# Power.net
KiCad netlist of a schematic drawn in Altium Designer
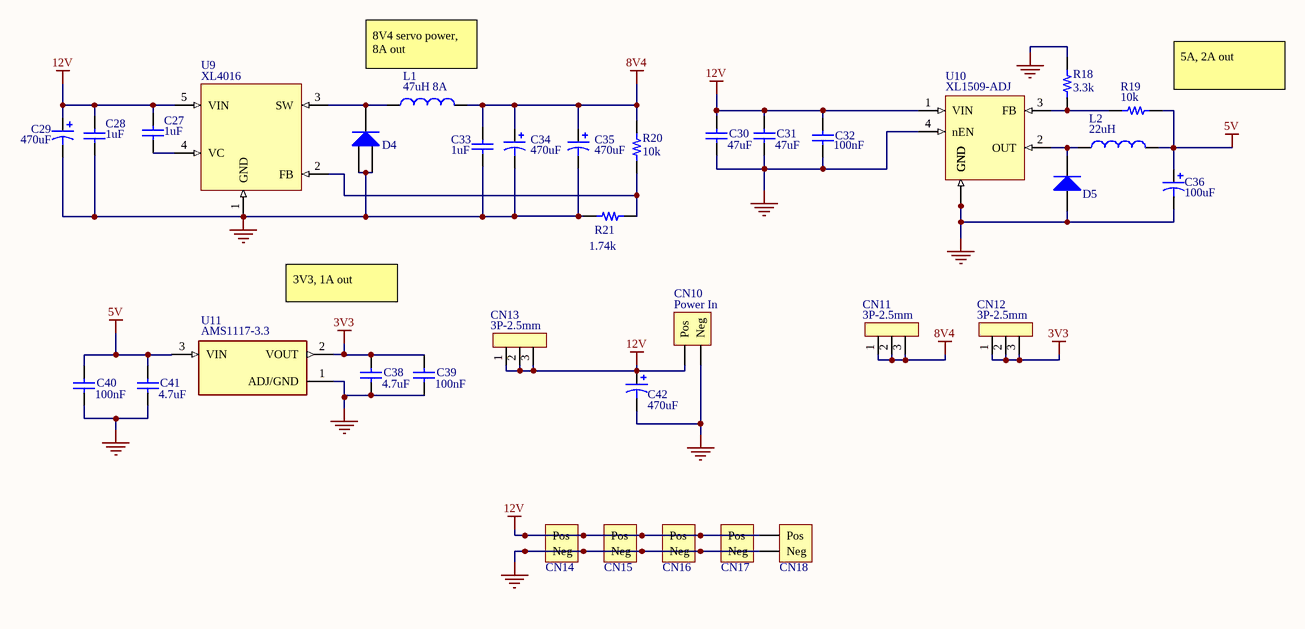
[diagram p0: Power.SchDoc]

(export (version "E")
  (design (tool "Eeschema 10.0.6"))
  (components
    (comp (ref "C27")
      (value "1uF")
      (footprint "0402")
      (fields (field (name "Comment") "Cap") (field (name "PUBLISHER") "Altium Limited"))
      (libsource (lib "Parts") (part "Cap"))
    )
    (comp (ref "C28")
      (value "1uF")
      (footprint "0402")
      (fields (field (name "Comment") "Cap") (field (name "PUBLISHER") "Altium Limited"))
      (libsource (lib "Parts") (part "Cap"))
    )
    (comp (ref "C29")
      (value "470uF")
      (footprint "10x12mm-Electrolytic")
      (libsource (lib "Parts") (part "Polarised Capacitor"))
    )
    (comp (ref "C30")
      (value "47uF")
      (footprint "1206")
      (fields (field (name "Comment") "Cap") (field (name "PUBLISHER") "Altium Limited"))
      (libsource (lib "Parts") (part "Cap"))
    )
    (comp (ref "C31")
      (value "47uF")
      (footprint "1206")
      (fields (field (name "Comment") "Cap") (field (name "PUBLISHER") "Altium Limited"))
      (libsource (lib "Parts") (part "Cap"))
    )
    (comp (ref "C32")
      (value "100nF")
      (footprint "0402")
      (fields (field (name "Comment") "Cap") (field (name "PUBLISHER") "Altium Limited"))
      (libsource (lib "Parts") (part "Cap"))
    )
    (comp (ref "C33")
      (value "1uF")
      (footprint "0402")
      (fields (field (name "Comment") "Cap") (field (name "PUBLISHER") "Altium Limited"))
      (libsource (lib "Parts") (part "Cap"))
    )
    (comp (ref "C34")
      (value "470uF")
      (footprint "10x12mm-Electrolytic")
      (libsource (lib "Parts") (part "Polarised Capacitor"))
    )
    (comp (ref "C35")
      (value "470uF")
      (footprint "10x12mm-Electrolytic")
      (libsource (lib "Parts") (part "Polarised Capacitor"))
    )
    (comp (ref "C36")
      (value "100uF")
      (footprint "10x12mm-Electrolytic")
      (libsource (lib "Parts") (part "Polarised Capacitor"))
    )
    (comp (ref "C38")
      (value "4.7uF")
      (footprint "0805 - duplicate")
      (fields (field (name "Comment") "Cap") (field (name "PUBLISHER") "Altium Limited"))
      (libsource (lib "Parts") (part "Cap"))
    )
    (comp (ref "C39")
      (value "100nF")
      (footprint "0402")
      (fields (field (name "Comment") "Cap") (field (name "PUBLISHER") "Altium Limited"))
      (libsource (lib "Parts") (part "Cap"))
    )
    (comp (ref "C40")
      (value "100nF")
      (footprint "0402")
      (fields (field (name "Comment") "Cap") (field (name "PUBLISHER") "Altium Limited"))
      (libsource (lib "Parts") (part "Cap"))
    )
    (comp (ref "C41")
      (value "4.7uF")
      (footprint "0805 - duplicate")
      (fields (field (name "Comment") "Cap") (field (name "PUBLISHER") "Altium Limited"))
      (libsource (lib "Parts") (part "Cap"))
    )
    (comp (ref "C42")
      (value "470uF")
      (footprint "10x12mm-Electrolytic")
      (libsource (lib "Parts") (part "Polarised Capacitor"))
    )
    (comp (ref "CN10")
      (value "Power In")
      (footprint "Power_Leads")
      (libsource (lib "") (part "JST_Leads_In_1"))
    )
    (comp (ref "CN11") (value "3P-2.5mm") (footprint "2.5mm-3P") (libsource (lib "Parts") (part "3P-2.5mm")))
    (comp (ref "CN12") (value "3P-2.5mm") (footprint "2.5mm-3P") (libsource (lib "Parts") (part "3P-2.5mm")))
    (comp (ref "CN13") (value "3P-2.5mm") (footprint "2.5mm-3P") (libsource (lib "Parts") (part "3P-2.5mm")))
    (comp (ref "CN14")
      (value "JST_Leads_In")
      (footprint "Power_Leads")
      (libsource (lib "Parts") (part "JST_Leads_In"))
    )
    (comp (ref "CN15")
      (value "JST_Leads_In")
      (footprint "Power_Leads")
      (libsource (lib "Parts") (part "JST_Leads_In"))
    )
    (comp (ref "CN16")
      (value "JST_Leads_In")
      (footprint "Power_Leads")
      (libsource (lib "Parts") (part "JST_Leads_In"))
    )
    (comp (ref "CN17")
      (value "JST_Leads_In")
      (footprint "Power_Leads")
      (libsource (lib "Parts") (part "JST_Leads_In"))
    )
    (comp (ref "CN18")
      (value "JST_Leads_In")
      (footprint "Power_Leads")
      (libsource (lib "Parts") (part "JST_Leads_In"))
    )
    (comp (ref "D4")
      (value "Diode")
      (footprint "PowerDi5")
      (fields (field (name "PUBLISHER") "Altium Limited"))
      (libsource (lib "Parts") (part "Diode"))
    )
    (comp (ref "D5")
      (value "SS24")
      (footprint "DO-214AA")
      (description "2A Schottky Diode")
      (libsource (lib "Parts") (part "SS24"))
    )
    (comp (ref "L1")
      (value "47uH 8A")
      (footprint "18x16-9-Inductor")
      (description "TMPC1707")
      (libsource (lib "Parts") (part "SMD Inductor 18x16.9"))
    )
    (comp (ref "L2")
      (value "22uH")
      (footprint "71x66-Inductor")
      (libsource (lib "Parts") (part "22uH Inductor, 7.1*6.6"))
    )
    (comp (ref "R18")
      (value "3.3k")
      (footprint "0805 - duplicate")
      (libsource (lib "Parts") (part "Resistor"))
    )
    (comp (ref "R19")
      (value "10k")
      (footprint "0805 - duplicate")
      (libsource (lib "Parts") (part "Resistor"))
    )
    (comp (ref "R20")
      (value "10k")
      (footprint "0805 - duplicate")
      (libsource (lib "Parts") (part "Resistor"))
    )
    (comp (ref "R21")
      (value "1.74k")
      (footprint "0805 - duplicate")
      (libsource (lib "Parts") (part "Resistor"))
    )
    (comp (ref "U9")
      (value "XL4016")
      (footprint "TO220-5L")
      (description "8A Buck COnverter")
      (libsource (lib "Parts") (part "XL4016"))
    )
    (comp (ref "U10")
      (value "XL1509-ADJ")
      (footprint "SOP8-MT3420")
      (libsource (lib "Parts") (part "XL1509-5"))
    )
    (comp (ref "U11")
      (value "AMS1117-3.3")
      (footprint "SOT229P700X180-4N")
      (description "Sot223/Pkg 1-Amp 3.3-Volt Low Drop Out Voltage Regulatator")
      (fields (field (name "MF") "Advanced Monolithic Systems"))
      (libsource (lib "Parts") (part "AMS1117-3.3"))
    )
  )
  (nets
    (net (code "1") (name "3V3") (class "Default")
      (node (ref "C38") (pin "2") (pinfunction "2_2") (pintype "passive"))
      (node (ref "C39") (pin "2") (pinfunction "2_2") (pintype "passive"))
      (node (ref "CN12") (pin "1") (pintype "passive"))
      (node (ref "CN12") (pin "2") (pintype "passive"))
      (node (ref "CN12") (pin "3") (pintype "passive"))
      (node (ref "U11") (pin "2") (pinfunction "VOUT_2") (pintype "output"))
    )
    (net (code "2") (name "5V") (class "Default")
      (node (ref "C36") (pin "1") (pinfunction "1_1") (pintype "passive"))
      (node (ref "C40") (pin "2") (pinfunction "2_2") (pintype "passive"))
      (node (ref "C41") (pin "2") (pinfunction "2_2") (pintype "passive"))
      (node (ref "L2") (pin "2") (pinfunction "2_2") (pintype "passive"))
      (node (ref "R19") (pin "2") (pinfunction "2_2") (pintype "passive"))
      (node (ref "U11") (pin "3") (pinfunction "VIN_3") (pintype "input"))
    )
    (net (code "3") (name "8V4") (class "Default")
      (node (ref "C33") (pin "2") (pinfunction "2_2") (pintype "passive"))
      (node (ref "C34") (pin "1") (pinfunction "1_1") (pintype "passive"))
      (node (ref "C35") (pin "1") (pinfunction "1_1") (pintype "passive"))
      (node (ref "CN11") (pin "1") (pintype "passive"))
      (node (ref "CN11") (pin "2") (pintype "passive"))
      (node (ref "CN11") (pin "3") (pintype "passive"))
      (node (ref "L1") (pin "2") (pinfunction "2_2") (pintype "passive"))
      (node (ref "R20") (pin "2") (pinfunction "2_2") (pintype "passive"))
    )
    (net (code "4") (name "12V") (class "Default")
      (node (ref "C27") (pin "2") (pinfunction "2_2") (pintype "passive"))
      (node (ref "C28") (pin "2") (pinfunction "2_2") (pintype "passive"))
      (node (ref "C29") (pin "1") (pinfunction "1_1") (pintype "passive"))
      (node (ref "C30") (pin "2") (pinfunction "2_2") (pintype "passive"))
      (node (ref "C31") (pin "2") (pinfunction "2_2") (pintype "passive"))
      (node (ref "C32") (pin "2") (pinfunction "2_2") (pintype "passive"))
      (node (ref "C42") (pin "1") (pinfunction "1_1") (pintype "passive"))
      (node (ref "CN10") (pin "A") (pinfunction "Pos_A") (pintype "passive"))
      (node (ref "CN13") (pin "1") (pintype "passive"))
      (node (ref "CN13") (pin "2") (pintype "passive"))
      (node (ref "CN13") (pin "3") (pintype "passive"))
      (node (ref "CN14") (pin "A") (pinfunction "Pos_A") (pintype "passive"))
      (node (ref "CN15") (pin "A") (pinfunction "Pos_A") (pintype "passive"))
      (node (ref "CN16") (pin "A") (pinfunction "Pos_A") (pintype "passive"))
      (node (ref "CN17") (pin "A") (pinfunction "Pos_A") (pintype "passive"))
      (node (ref "CN18") (pin "A") (pinfunction "Pos_A") (pintype "passive"))
      (node (ref "U10") (pin "1") (pinfunction "VIN_1") (pintype "input"))
      (node (ref "U9") (pin "5") (pinfunction "VIN_5") (pintype "input"))
    )
    (net (code "5") (name "GND") (class "Default")
      (node (ref "C28") (pin "1") (pinfunction "1_1") (pintype "passive"))
      (node (ref "C29") (pin "2") (pinfunction "2_2") (pintype "passive"))
      (node (ref "C30") (pin "1") (pinfunction "1_1") (pintype "passive"))
      (node (ref "C31") (pin "1") (pinfunction "1_1") (pintype "passive"))
      (node (ref "C32") (pin "1") (pinfunction "1_1") (pintype "passive"))
      (node (ref "C33") (pin "1") (pinfunction "1_1") (pintype "passive"))
      (node (ref "C34") (pin "2") (pinfunction "2_2") (pintype "passive"))
      (node (ref "C35") (pin "2") (pinfunction "2_2") (pintype "passive"))
      (node (ref "C36") (pin "2") (pinfunction "2_2") (pintype "passive"))
      (node (ref "C38") (pin "1") (pinfunction "1_1") (pintype "passive"))
      (node (ref "C39") (pin "1") (pinfunction "1_1") (pintype "passive"))
      (node (ref "C40") (pin "1") (pinfunction "1_1") (pintype "passive"))
      (node (ref "C41") (pin "1") (pinfunction "1_1") (pintype "passive"))
      (node (ref "C42") (pin "2") (pinfunction "2_2") (pintype "passive"))
      (node (ref "CN10") (pin "K") (pinfunction "Neg_K") (pintype "passive"))
      (node (ref "CN14") (pin "K") (pinfunction "Neg_K") (pintype "passive"))
      (node (ref "CN15") (pin "K") (pinfunction "Neg_K") (pintype "passive"))
      (node (ref "CN16") (pin "K") (pinfunction "Neg_K") (pintype "passive"))
      (node (ref "CN17") (pin "K") (pinfunction "Neg_K") (pintype "passive"))
      (node (ref "CN18") (pin "K") (pinfunction "Neg_K") (pintype "passive"))
      (node (ref "D4") (pin "1") (pinfunction "A_1") (pintype "passive"))
      (node (ref "D4") (pin "2") (pinfunction "A_2") (pintype "passive"))
      (node (ref "D5") (pin "A") (pinfunction "A_A") (pintype "passive"))
      (node (ref "R18") (pin "2") (pinfunction "2_2") (pintype "passive"))
      (node (ref "R21") (pin "1") (pinfunction "1_1") (pintype "passive"))
      (node (ref "U10") (pin "4") (pinfunction "nEN_4") (pintype "input"))
      (node (ref "U10") (pin "5") (pinfunction "GND_5") (pintype "input"))
      (node (ref "U10") (pin "6") (pinfunction "GND_6") (pintype "input"))
      (node (ref "U10") (pin "7") (pinfunction "GND_7") (pintype "input"))
      (node (ref "U10") (pin "8") (pinfunction "GND_8") (pintype "input"))
      (node (ref "U11") (pin "1") (pinfunction "ADJ/GND_1") (pintype "power_in"))
      (node (ref "U9") (pin "1") (pinfunction "GND_1") (pintype "input"))
    )
    (net (code "6") (name "Net-(D4-K)") (class "Default")
      (node (ref "D4") (pin "3") (pinfunction "K_3") (pintype "passive"))
      (node (ref "L1") (pin "1") (pinfunction "1_1") (pintype "passive"))
      (node (ref "U9") (pin "3") (pinfunction "SW_3") (pintype "input"))
    )
    (net (code "7") (name "Net-(U9-FB)") (class "Default")
      (node (ref "R20") (pin "1") (pinfunction "1_1") (pintype "passive"))
      (node (ref "R21") (pin "2") (pinfunction "2_2") (pintype "passive"))
      (node (ref "U9") (pin "2") (pinfunction "FB_2") (pintype "input"))
    )
    (net (code "8") (name "Net-(U9-VC)") (class "Default")
      (node (ref "C27") (pin "1") (pinfunction "1_1") (pintype "passive"))
      (node (ref "U9") (pin "4") (pinfunction "VC_4") (pintype "input"))
    )
    (net (code "9") (name "Net-(U10-FB)") (class "Default")
      (node (ref "R18") (pin "1") (pinfunction "1_1") (pintype "passive"))
      (node (ref "R19") (pin "1") (pinfunction "1_1") (pintype "passive"))
      (node (ref "U10") (pin "3") (pinfunction "FB_3") (pintype "input"))
    )
    (net (code "10") (name "Net-(U10-OUT)") (class "Default")
      (node (ref "D5") (pin "K") (pinfunction "K_K") (pintype "passive"))
      (node (ref "L2") (pin "1") (pinfunction "1_1") (pintype "passive"))
      (node (ref "U10") (pin "2") (pinfunction "OUT_2") (pintype "input"))
    )
  )
)
